# SOC_IO.net
KiCad netlist of a schematic drawn in Altium Designer
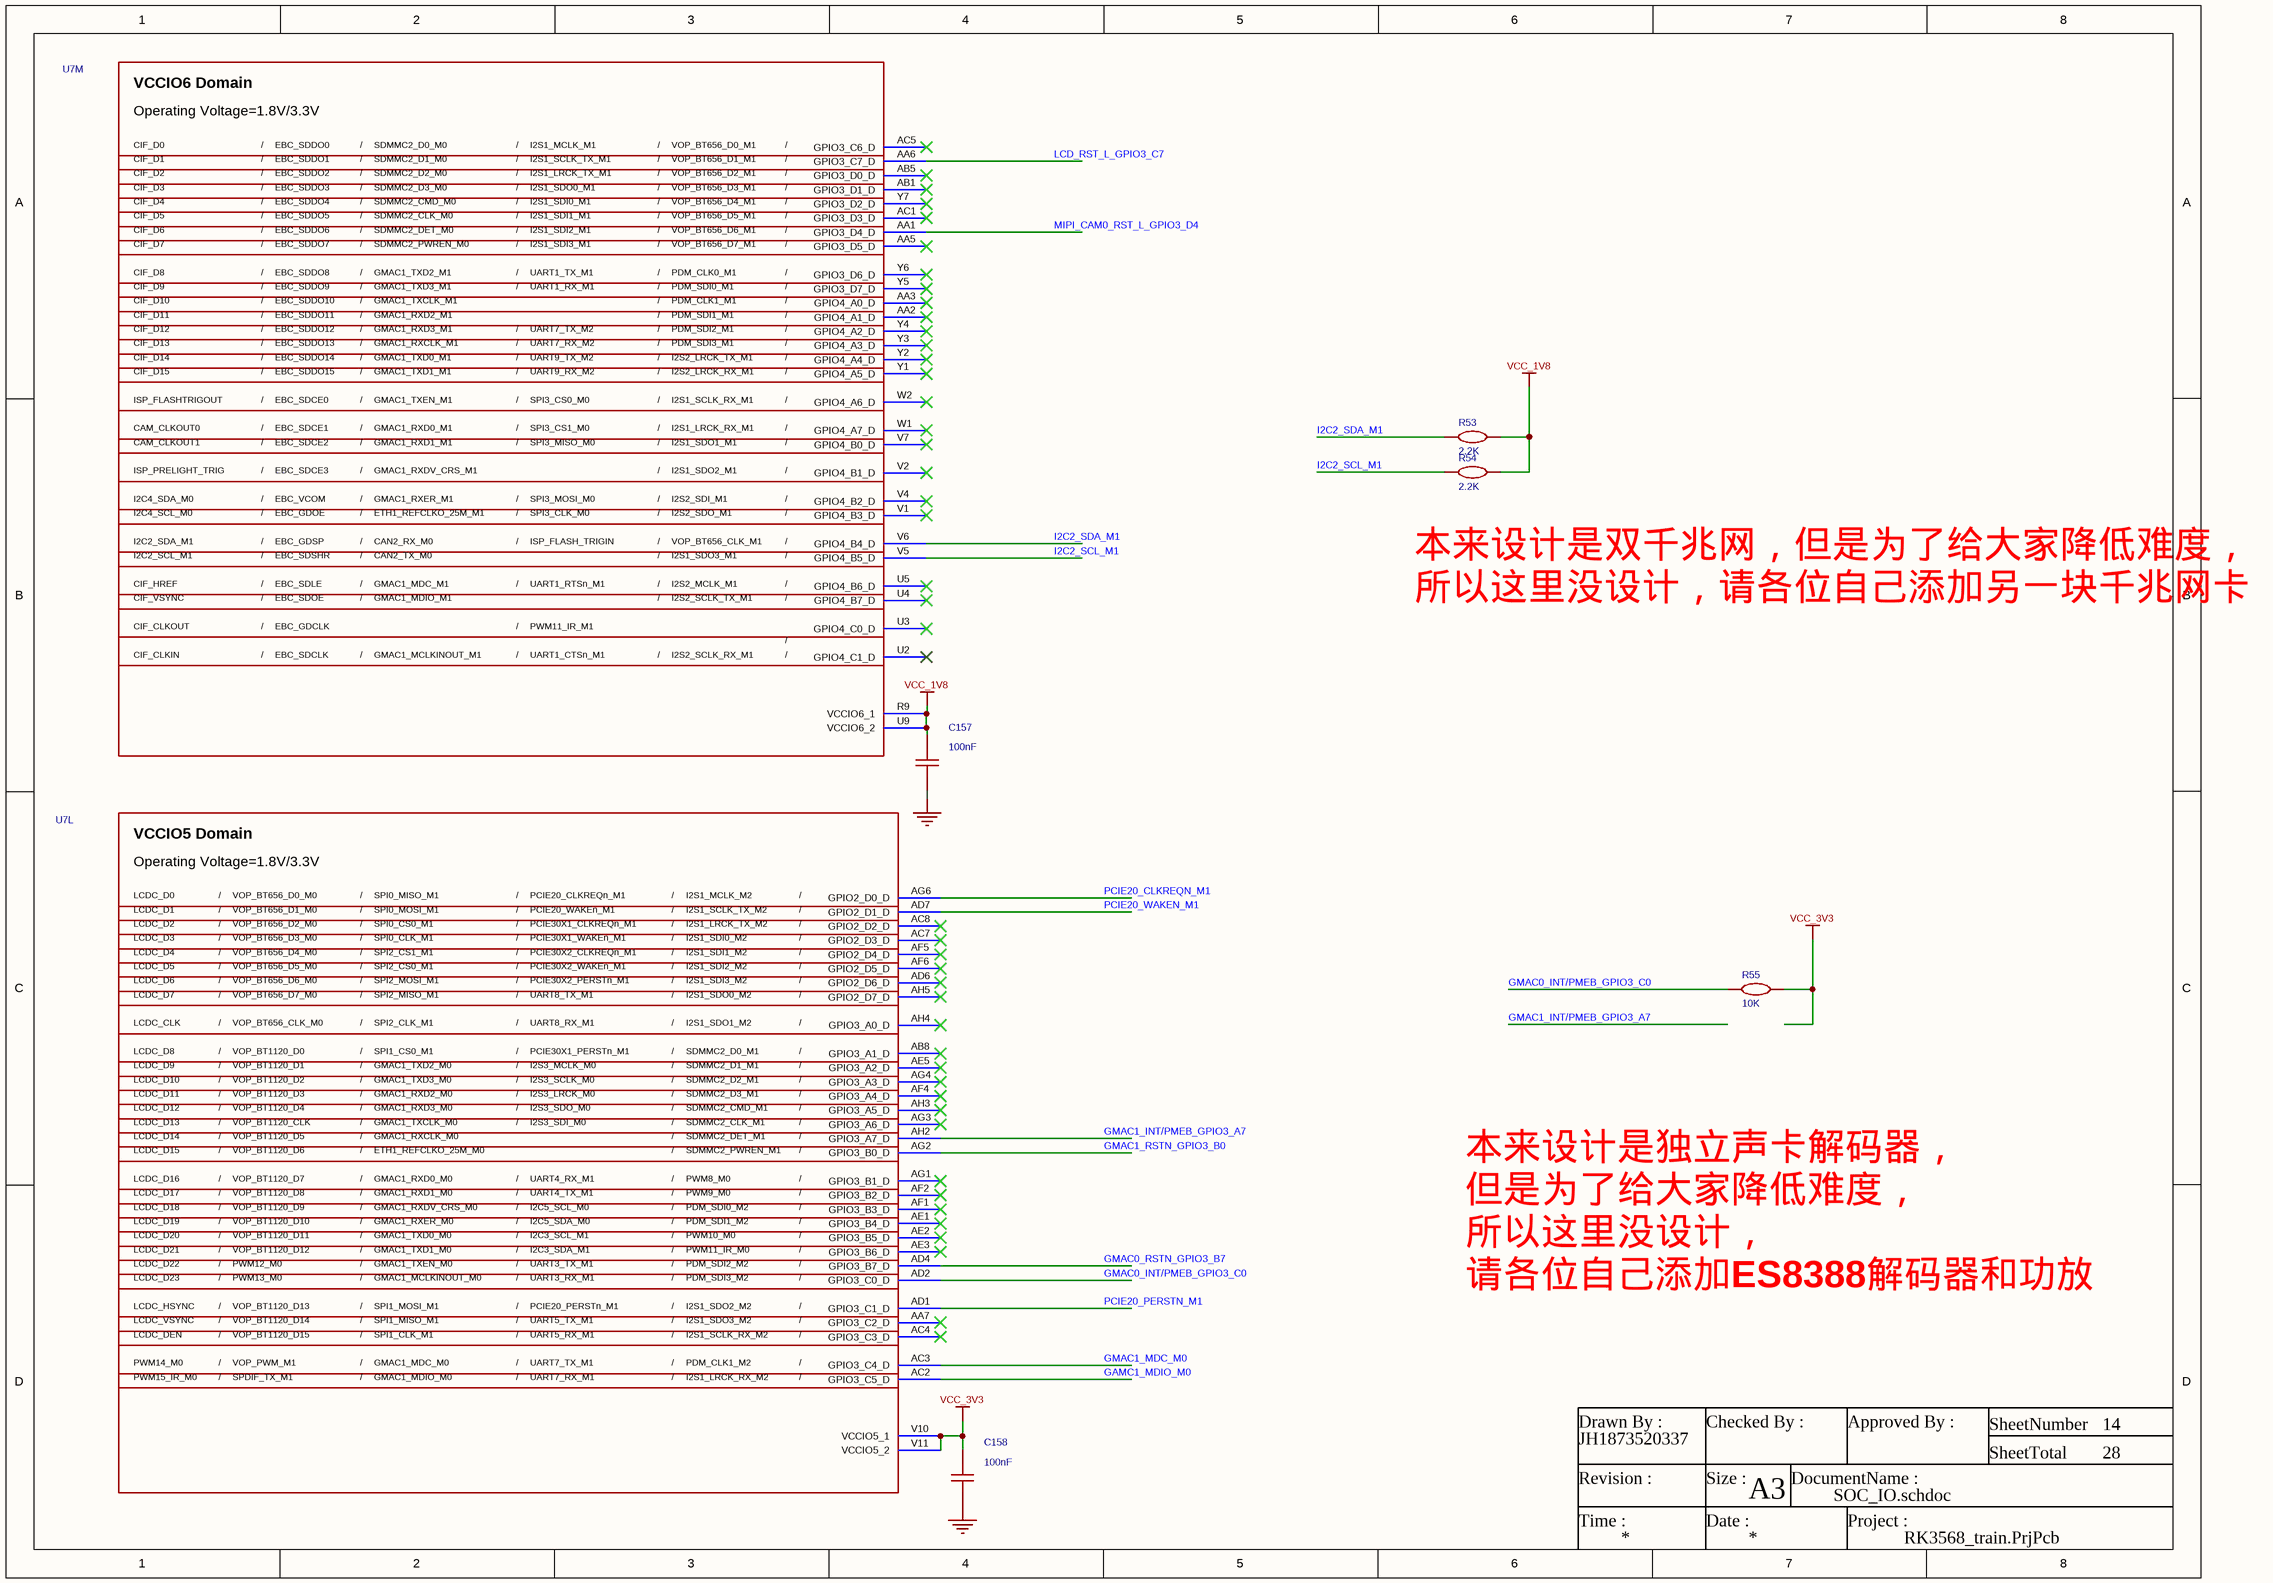
[diagram p0: SOC_IO.schdoc]

(export (version "E")
  (design (tool "Eeschema 10.0.6"))
  (components
    (comp (ref "C157")
      (value "100nF")
      (footprint "C0201")
      (description "容值:4.7uF;精度:±20%;额定电压:6.3V;温度系数:X5R;")
      (fields
        (field (name "MANUFACTURER") "muRata(村田)")
        (field (name "MANUFACTURERPART") "GRM035R60J475ME15D")
      )
      (libsource (lib "altium-import") (part "root_0_GRM035R60J475ME15D_"))
    )
    (comp (ref "C158")
      (value "100nF")
      (footprint "C0201")
      (description "容值:4.7uF;精度:±20%;额定电压:6.3V;温度系数:X5R;")
      (fields
        (field (name "MANUFACTURER") "muRata(村田)")
        (field (name "MANUFACTURERPART") "GRM035R60J475ME15D")
      )
      (libsource (lib "altium-import") (part "root_0_GRM035R60J475ME15D_"))
    )
    (comp (ref "R53")
      (value "2.2K")
      (footprint "R0402")
      (libsource (lib "altium-import") (part "root_0_Res_0402_"))
    )
    (comp (ref "R54")
      (value "2.2K")
      (footprint "R0402")
      (libsource (lib "altium-import") (part "root_0_Res_0402_"))
    )
    (comp (ref "R55")
      (value "10K")
      (footprint "R0402")
      (libsource (lib "altium-import") (part "root_0_Res_0402_"))
    )
    (comp (ref "U7")
      (value "RK3568")
      (footprint "BGA-636_L19.0-W19.0-P0.65-BL")
      (libsource (lib "altium-import") (part "root_0_RK3568_"))
    )
  )
  (nets
    (net (code "2") (name "/GAMC1_MDIO_M0") (class "Default")
      (node (ref "U7") (pin "AC2") (pinfunction "GPIO3_C5_D_AC2") (pintype "passive"))
    )
    (net (code "3") (name "/GMAC0_INT{slash}PMEB_GPIO3_C0") (class "Default")
      (node (ref "R55") (pin "1") (pinfunction "1_1") (pintype "passive"))
      (node (ref "U7") (pin "AD2") (pinfunction "GPIO3_C0_D_AD2") (pintype "passive"))
    )
    (net (code "4") (name "/GMAC0_RSTN_GPIO3_B7") (class "Default")
      (node (ref "U7") (pin "AD4") (pinfunction "GPIO3_B7_D_AD4") (pintype "passive"))
    )
    (net (code "5") (name "/GMAC1_INT{slash}PMEB_GPIO3_A7") (class "Default")
      (node (ref "U7") (pin "AH2") (pinfunction "GPIO3_A7_D_AH2") (pintype "passive"))
    )
    (net (code "6") (name "/GMAC1_MDC_M0") (class "Default")
      (node (ref "U7") (pin "AC3") (pinfunction "GPIO3_C4_D_AC3") (pintype "passive"))
    )
    (net (code "7") (name "/GMAC1_RSTN_GPIO3_B0") (class "Default")
      (node (ref "U7") (pin "AG2") (pinfunction "GPIO3_B0_D_AG2") (pintype "passive"))
    )
    (net (code "8") (name "/I2C2_SCL_M1") (class "Default")
      (node (ref "R54") (pin "1") (pinfunction "1_1") (pintype "passive"))
      (node (ref "U7") (pin "V5") (pinfunction "GPIO4_B5_D_V5") (pintype "passive"))
    )
    (net (code "9") (name "/I2C2_SDA_M1") (class "Default")
      (node (ref "R53") (pin "1") (pinfunction "1_1") (pintype "passive"))
      (node (ref "U7") (pin "V6") (pinfunction "GPIO4_B4_D_V6") (pintype "passive"))
    )
    (net (code "10") (name "/LCD_RST_L_GPIO3_C7") (class "Default")
      (node (ref "U7") (pin "AA6") (pinfunction "GPIO3_C7_D_AA6") (pintype "passive"))
    )
    (net (code "11") (name "/MIPI_CAM0_RST_L_GPIO3_D4") (class "Default")
      (node (ref "U7") (pin "AA1") (pinfunction "GPIO3_D4_D_AA1") (pintype "passive"))
    )
    (net (code "12") (name "/PCIE20_CLKREQN_M1") (class "Default")
      (node (ref "U7") (pin "AG6") (pinfunction "GPIO2_D0_D_AG6") (pintype "passive"))
    )
    (net (code "13") (name "/PCIE20_PERSTN_M1") (class "Default")
      (node (ref "U7") (pin "AD1") (pinfunction "GPIO3_C1_D_AD1") (pintype "passive"))
    )
    (net (code "14") (name "/PCIE20_WAKEN_M1") (class "Default")
      (node (ref "U7") (pin "AD7") (pinfunction "GPIO2_D1_D_AD7") (pintype "passive"))
    )
    (net (code "15") (name "GND") (class "Default")
      (node (ref "C157") (pin "1") (pinfunction "1_1") (pintype "passive"))
      (node (ref "C158") (pin "1") (pinfunction "1_1") (pintype "passive"))
    )
    (net (code "16") (name "VCC_1V8") (class "Default")
      (node (ref "C157") (pin "2") (pinfunction "2_2") (pintype "passive"))
      (node (ref "R53") (pin "2") (pinfunction "2_2") (pintype "passive"))
      (node (ref "R54") (pin "2") (pinfunction "2_2") (pintype "passive"))
      (node (ref "U7") (pin "R9") (pinfunction "VCCIO6_1_R9") (pintype "passive"))
      (node (ref "U7") (pin "U9") (pinfunction "VCCIO6_2_U9") (pintype "passive"))
    )
    (net (code "17") (name "VCC_3V3") (class "Default")
      (node (ref "C158") (pin "2") (pinfunction "2_2") (pintype "passive"))
      (node (ref "R55") (pin "2") (pinfunction "2_2") (pintype "passive"))
      (node (ref "U7") (pin "V10") (pinfunction "VCCIO5_1_V10") (pintype "passive"))
      (node (ref "U7") (pin "V11") (pinfunction "VCCIO5_2_V11") (pintype "passive"))
    )
    (net (code "18") (name "unconnected-(U7L-GPIO2_D2_D-PadAC8)") (class "Default")
      (node (ref "U7") (pin "AC8") (pinfunction "GPIO2_D2_D_AC8") (pintype "passive+no_connect"))
    )
    (net (code "19") (name "unconnected-(U7L-GPIO2_D3_D-PadAC7)") (class "Default")
      (node (ref "U7") (pin "AC7") (pinfunction "GPIO2_D3_D_AC7") (pintype "passive+no_connect"))
    )
    (net (code "20") (name "unconnected-(U7L-GPIO2_D4_D-PadAF5)") (class "Default")
      (node (ref "U7") (pin "AF5") (pinfunction "GPIO2_D4_D_AF5") (pintype "passive+no_connect"))
    )
    (net (code "21") (name "unconnected-(U7L-GPIO2_D5_D-PadAF6)") (class "Default")
      (node (ref "U7") (pin "AF6") (pinfunction "GPIO2_D5_D_AF6") (pintype "passive+no_connect"))
    )
    (net (code "22") (name "unconnected-(U7L-GPIO2_D6_D-PadAD6)") (class "Default")
      (node (ref "U7") (pin "AD6") (pinfunction "GPIO2_D6_D_AD6") (pintype "passive+no_connect"))
    )
    (net (code "23") (name "unconnected-(U7L-GPIO2_D7_D-PadAH5)") (class "Default")
      (node (ref "U7") (pin "AH5") (pinfunction "GPIO2_D7_D_AH5") (pintype "passive+no_connect"))
    )
    (net (code "24") (name "unconnected-(U7L-GPIO3_A0_D-PadAH4)") (class "Default")
      (node (ref "U7") (pin "AH4") (pinfunction "GPIO3_A0_D_AH4") (pintype "passive+no_connect"))
    )
    (net (code "25") (name "unconnected-(U7L-GPIO3_A1_D-PadAB8)") (class "Default")
      (node (ref "U7") (pin "AB8") (pinfunction "GPIO3_A1_D_AB8") (pintype "passive+no_connect"))
    )
    (net (code "26") (name "unconnected-(U7L-GPIO3_A2_D-PadAE5)") (class "Default")
      (node (ref "U7") (pin "AE5") (pinfunction "GPIO3_A2_D_AE5") (pintype "passive+no_connect"))
    )
    (net (code "27") (name "unconnected-(U7L-GPIO3_A3_D-PadAG4)") (class "Default")
      (node (ref "U7") (pin "AG4") (pinfunction "GPIO3_A3_D_AG4") (pintype "passive+no_connect"))
    )
    (net (code "28") (name "unconnected-(U7L-GPIO3_A4_D-PadAF4)") (class "Default")
      (node (ref "U7") (pin "AF4") (pinfunction "GPIO3_A4_D_AF4") (pintype "passive+no_connect"))
    )
    (net (code "29") (name "unconnected-(U7L-GPIO3_A5_D-PadAH3)") (class "Default")
      (node (ref "U7") (pin "AH3") (pinfunction "GPIO3_A5_D_AH3") (pintype "passive+no_connect"))
    )
    (net (code "30") (name "unconnected-(U7L-GPIO3_A6_D-PadAG3)") (class "Default")
      (node (ref "U7") (pin "AG3") (pinfunction "GPIO3_A6_D_AG3") (pintype "passive+no_connect"))
    )
    (net (code "31") (name "unconnected-(U7L-GPIO3_B1_D-PadAG1)") (class "Default")
      (node (ref "U7") (pin "AG1") (pinfunction "GPIO3_B1_D_AG1") (pintype "passive+no_connect"))
    )
    (net (code "32") (name "unconnected-(U7L-GPIO3_B2_D-PadAF2)") (class "Default")
      (node (ref "U7") (pin "AF2") (pinfunction "GPIO3_B2_D_AF2") (pintype "passive+no_connect"))
    )
    (net (code "33") (name "unconnected-(U7L-GPIO3_B3_D-PadAF1)") (class "Default")
      (node (ref "U7") (pin "AF1") (pinfunction "GPIO3_B3_D_AF1") (pintype "passive+no_connect"))
    )
    (net (code "34") (name "unconnected-(U7L-GPIO3_B4_D-PadAE1)") (class "Default")
      (node (ref "U7") (pin "AE1") (pinfunction "GPIO3_B4_D_AE1") (pintype "passive+no_connect"))
    )
    (net (code "35") (name "unconnected-(U7L-GPIO3_B5_D-PadAE2)") (class "Default")
      (node (ref "U7") (pin "AE2") (pinfunction "GPIO3_B5_D_AE2") (pintype "passive+no_connect"))
    )
    (net (code "36") (name "unconnected-(U7L-GPIO3_B6_D-PadAE3)") (class "Default")
      (node (ref "U7") (pin "AE3") (pinfunction "GPIO3_B6_D_AE3") (pintype "passive+no_connect"))
    )
    (net (code "37") (name "unconnected-(U7L-GPIO3_C2_D-PadAA7)") (class "Default")
      (node (ref "U7") (pin "AA7") (pinfunction "GPIO3_C2_D_AA7") (pintype "passive+no_connect"))
    )
    (net (code "38") (name "unconnected-(U7L-GPIO3_C3_D-PadAC4)") (class "Default")
      (node (ref "U7") (pin "AC4") (pinfunction "GPIO3_C3_D_AC4") (pintype "passive+no_connect"))
    )
    (net (code "39") (name "unconnected-(U7M-GPIO3_C6_D-PadAC5)") (class "Default")
      (node (ref "U7") (pin "AC5") (pinfunction "GPIO3_C6_D_AC5") (pintype "passive+no_connect"))
    )
    (net (code "40") (name "unconnected-(U7M-GPIO3_D0_D-PadAB5)") (class "Default")
      (node (ref "U7") (pin "AB5") (pinfunction "GPIO3_D0_D_AB5") (pintype "passive+no_connect"))
    )
    (net (code "41") (name "unconnected-(U7M-GPIO3_D1_D-PadAB1)") (class "Default")
      (node (ref "U7") (pin "AB1") (pinfunction "GPIO3_D1_D_AB1") (pintype "passive+no_connect"))
    )
    (net (code "42") (name "unconnected-(U7M-GPIO3_D2_D-PadY7)") (class "Default")
      (node (ref "U7") (pin "Y7") (pinfunction "GPIO3_D2_D_Y7") (pintype "passive+no_connect"))
    )
    (net (code "43") (name "unconnected-(U7M-GPIO3_D3_D-PadAC1)") (class "Default")
      (node (ref "U7") (pin "AC1") (pinfunction "GPIO3_D3_D_AC1") (pintype "passive+no_connect"))
    )
    (net (code "44") (name "unconnected-(U7M-GPIO3_D5_D-PadAA5)") (class "Default")
      (node (ref "U7") (pin "AA5") (pinfunction "GPIO3_D5_D_AA5") (pintype "passive+no_connect"))
    )
    (net (code "45") (name "unconnected-(U7M-GPIO3_D6_D-PadY6)") (class "Default")
      (node (ref "U7") (pin "Y6") (pinfunction "GPIO3_D6_D_Y6") (pintype "passive+no_connect"))
    )
    (net (code "46") (name "unconnected-(U7M-GPIO3_D7_D-PadY5)") (class "Default")
      (node (ref "U7") (pin "Y5") (pinfunction "GPIO3_D7_D_Y5") (pintype "passive+no_connect"))
    )
    (net (code "47") (name "unconnected-(U7M-GPIO4_A0_D-PadAA3)") (class "Default")
      (node (ref "U7") (pin "AA3") (pinfunction "GPIO4_A0_D_AA3") (pintype "passive+no_connect"))
    )
    (net (code "48") (name "unconnected-(U7M-GPIO4_A1_D-PadAA2)") (class "Default")
      (node (ref "U7") (pin "AA2") (pinfunction "GPIO4_A1_D_AA2") (pintype "passive+no_connect"))
    )
    (net (code "49") (name "unconnected-(U7M-GPIO4_A2_D-PadY4)") (class "Default")
      (node (ref "U7") (pin "Y4") (pinfunction "GPIO4_A2_D_Y4") (pintype "passive+no_connect"))
    )
    (net (code "50") (name "unconnected-(U7M-GPIO4_A3_D-PadY3)") (class "Default")
      (node (ref "U7") (pin "Y3") (pinfunction "GPIO4_A3_D_Y3") (pintype "passive+no_connect"))
    )
    (net (code "51") (name "unconnected-(U7M-GPIO4_A4_D-PadY2)") (class "Default")
      (node (ref "U7") (pin "Y2") (pinfunction "GPIO4_A4_D_Y2") (pintype "passive+no_connect"))
    )
    (net (code "52") (name "unconnected-(U7M-GPIO4_A5_D-PadY1)") (class "Default")
      (node (ref "U7") (pin "Y1") (pinfunction "GPIO4_A5_D_Y1") (pintype "passive+no_connect"))
    )
    (net (code "53") (name "unconnected-(U7M-GPIO4_A6_D-PadW2)") (class "Default")
      (node (ref "U7") (pin "W2") (pinfunction "GPIO4_A6_D_W2") (pintype "passive+no_connect"))
    )
    (net (code "54") (name "unconnected-(U7M-GPIO4_A7_D-PadW1)") (class "Default")
      (node (ref "U7") (pin "W1") (pinfunction "GPIO4_A7_D_W1") (pintype "passive+no_connect"))
    )
    (net (code "55") (name "unconnected-(U7M-GPIO4_B0_D-PadV7)") (class "Default")
      (node (ref "U7") (pin "V7") (pinfunction "GPIO4_B0_D_V7") (pintype "passive+no_connect"))
    )
    (net (code "56") (name "unconnected-(U7M-GPIO4_B1_D-PadV2)") (class "Default")
      (node (ref "U7") (pin "V2") (pinfunction "GPIO4_B1_D_V2") (pintype "passive+no_connect"))
    )
    (net (code "57") (name "unconnected-(U7M-GPIO4_B2_D-PadV4)") (class "Default")
      (node (ref "U7") (pin "V4") (pinfunction "GPIO4_B2_D_V4") (pintype "passive+no_connect"))
    )
    (net (code "58") (name "unconnected-(U7M-GPIO4_B3_D-PadV1)") (class "Default")
      (node (ref "U7") (pin "V1") (pinfunction "GPIO4_B3_D_V1") (pintype "passive+no_connect"))
    )
    (net (code "59") (name "unconnected-(U7M-GPIO4_B6_D-PadU5)") (class "Default")
      (node (ref "U7") (pin "U5") (pinfunction "GPIO4_B6_D_U5") (pintype "passive+no_connect"))
    )
    (net (code "60") (name "unconnected-(U7M-GPIO4_B7_D-PadU4)") (class "Default")
      (node (ref "U7") (pin "U4") (pinfunction "GPIO4_B7_D_U4") (pintype "passive+no_connect"))
    )
    (net (code "61") (name "unconnected-(U7M-GPIO4_C0_D-PadU3)") (class "Default")
      (node (ref "U7") (pin "U3") (pinfunction "GPIO4_C0_D_U3") (pintype "passive+no_connect"))
    )
    (net (code "62") (name "unconnected-(U7M-GPIO4_C1_D-PadU2)") (class "Default")
      (node (ref "U7") (pin "U2") (pinfunction "GPIO4_C1_D_U2") (pintype "passive+no_connect"))
    )
  )
)
